# buck_converter.net
KiCad netlist of a schematic drawn in Altium Designer
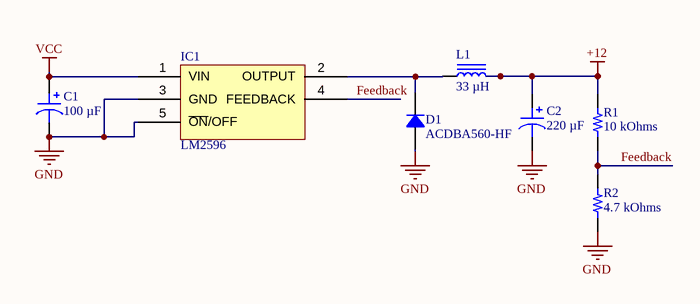
[diagram p0: buck_converter.SchDoc]

(export (version "E")
  (design (tool "Eeschema 10.0.6"))
  (components
    (comp (ref "C1")
      (value "100 µF")
      (footprint "CAP AL TH D8 L3.5 H12.5")
      (description "CAP ALUM 100UF 20% 63V RADIAL")
      (fields
        (field (name "PART NUMBER") "ECA-1JM101")
        (field (name "MANUFACTURER") "Panasonic Electronic Components")
      )
      (libsource (lib "Celestial Altium Library - altium_library") (part "Polarised Capacitor"))
    )
    (comp (ref "C2")
      (value "220 µF")
      (footprint "CAP AL TH D8 L3.5 H12.5")
      (description "CAP ALUM 220UF 20% 35V RADIAL")
      (fields
        (field (name "PART NUMBER") "ECA-1VM221")
        (field (name "MANUFACTURER") "Panasonic Electronic Components")
      )
      (libsource (lib "Celestial Altium Library - altium_library") (part "Polarised Capacitor"))
    )
    (comp (ref "D1")
      (value "ACDBA560-HF")
      (footprint "DO214AC SMA")
      (description "DIODE SCHOTTKY 60V 5A DO214AC")
      (fields (field (name "MANUFACTURER") "Comchip Technology"))
      (libsource (lib "Celestial Altium Library - altium_library") (part "Diode"))
    )
    (comp (ref "IC1")
      (value "LM2596")
      (footprint "TO263-5")
      (libsource (lib "Integrated_Library1") (part "LM2596"))
    )
    (comp (ref "L1")
      (value "33 µH")
      (footprint "BOURNS SRR1280")
      (description "FIXED IND 33UH 3.5A 57 MOHM SMD")
      (fields (field (name "PART NUMBER") "SRR1280-330M") (field (name "MANUFACTURER") "Bourns Inc."))
      (libsource (lib "Celestial Altium Library - altium_library") (part "Inductor"))
    )
    (comp (ref "R1")
      (value "10 kOhms")
      (footprint "RES 0805_2012")
      (description "RES SMD 10K OHM 0.1% 1/10W 0805")
      (fields
        (field (name "PART NUMBER") "CPF0805B10KE1")
        (field (name "MANUFACTURER") "TE Connectivity Passive Product")
      )
      (libsource (lib "Celestial Altium Library - altium_library") (part "Resistor"))
    )
    (comp (ref "R2")
      (value "4.7 kOhms")
      (footprint "RES 0805_2012")
      (description "RES 4.7K OHM 1% 1/3W 0805")
      (fields
        (field (name "PART NUMBER") "CRGP0805F4K7")
        (field (name "MANUFACTURER") "TE Connectivity Passive Product")
      )
      (libsource (lib "Celestial Altium Library - altium_library") (part "Resistor"))
    )
  )
  (nets
    (net (code "1") (name "+12") (class "Default")
      (node (ref "C2") (pin "1") (pinfunction "1_1") (pintype "passive"))
      (node (ref "L1") (pin "2") (pinfunction "2_2") (pintype "passive"))
      (node (ref "R1") (pin "2") (pinfunction "2_2") (pintype "passive"))
    )
    (net (code "2") (name "/Feedback") (class "Default")
      (node (ref "IC1") (pin "4") (pinfunction "FEEDBACK_4") (pintype "passive"))
      (node (ref "R1") (pin "1") (pinfunction "1_1") (pintype "passive"))
      (node (ref "R2") (pin "2") (pinfunction "2_2") (pintype "passive"))
    )
    (net (code "3") (name "GND") (class "Default")
      (node (ref "C1") (pin "2") (pinfunction "2_2") (pintype "passive"))
      (node (ref "C2") (pin "2") (pinfunction "2_2") (pintype "passive"))
      (node (ref "D1") (pin "1") (pinfunction "1_1") (pintype "passive"))
      (node (ref "IC1") (pin "3") (pinfunction "GND_3") (pintype "passive"))
      (node (ref "IC1") (pin "5") (pinfunction "~{ON}/OFF_5") (pintype "passive"))
      (node (ref "R2") (pin "1") (pinfunction "1_1") (pintype "passive"))
    )
    (net (code "4") (name "Net-(IC1-OUTPUT)") (class "Default")
      (node (ref "D1") (pin "2") (pinfunction "2_2") (pintype "passive"))
      (node (ref "IC1") (pin "2") (pinfunction "OUTPUT_2") (pintype "passive"))
      (node (ref "L1") (pin "1") (pinfunction "1_1") (pintype "passive"))
    )
    (net (code "5") (name "VCC") (class "Default")
      (node (ref "C1") (pin "1") (pinfunction "1_1") (pintype "passive"))
      (node (ref "IC1") (pin "1") (pinfunction "VIN_1") (pintype "passive"))
    )
  )
)
